# IMX7S_CPU_INTERFACES_1.net
KiCad netlist of a schematic drawn in Altium Designer
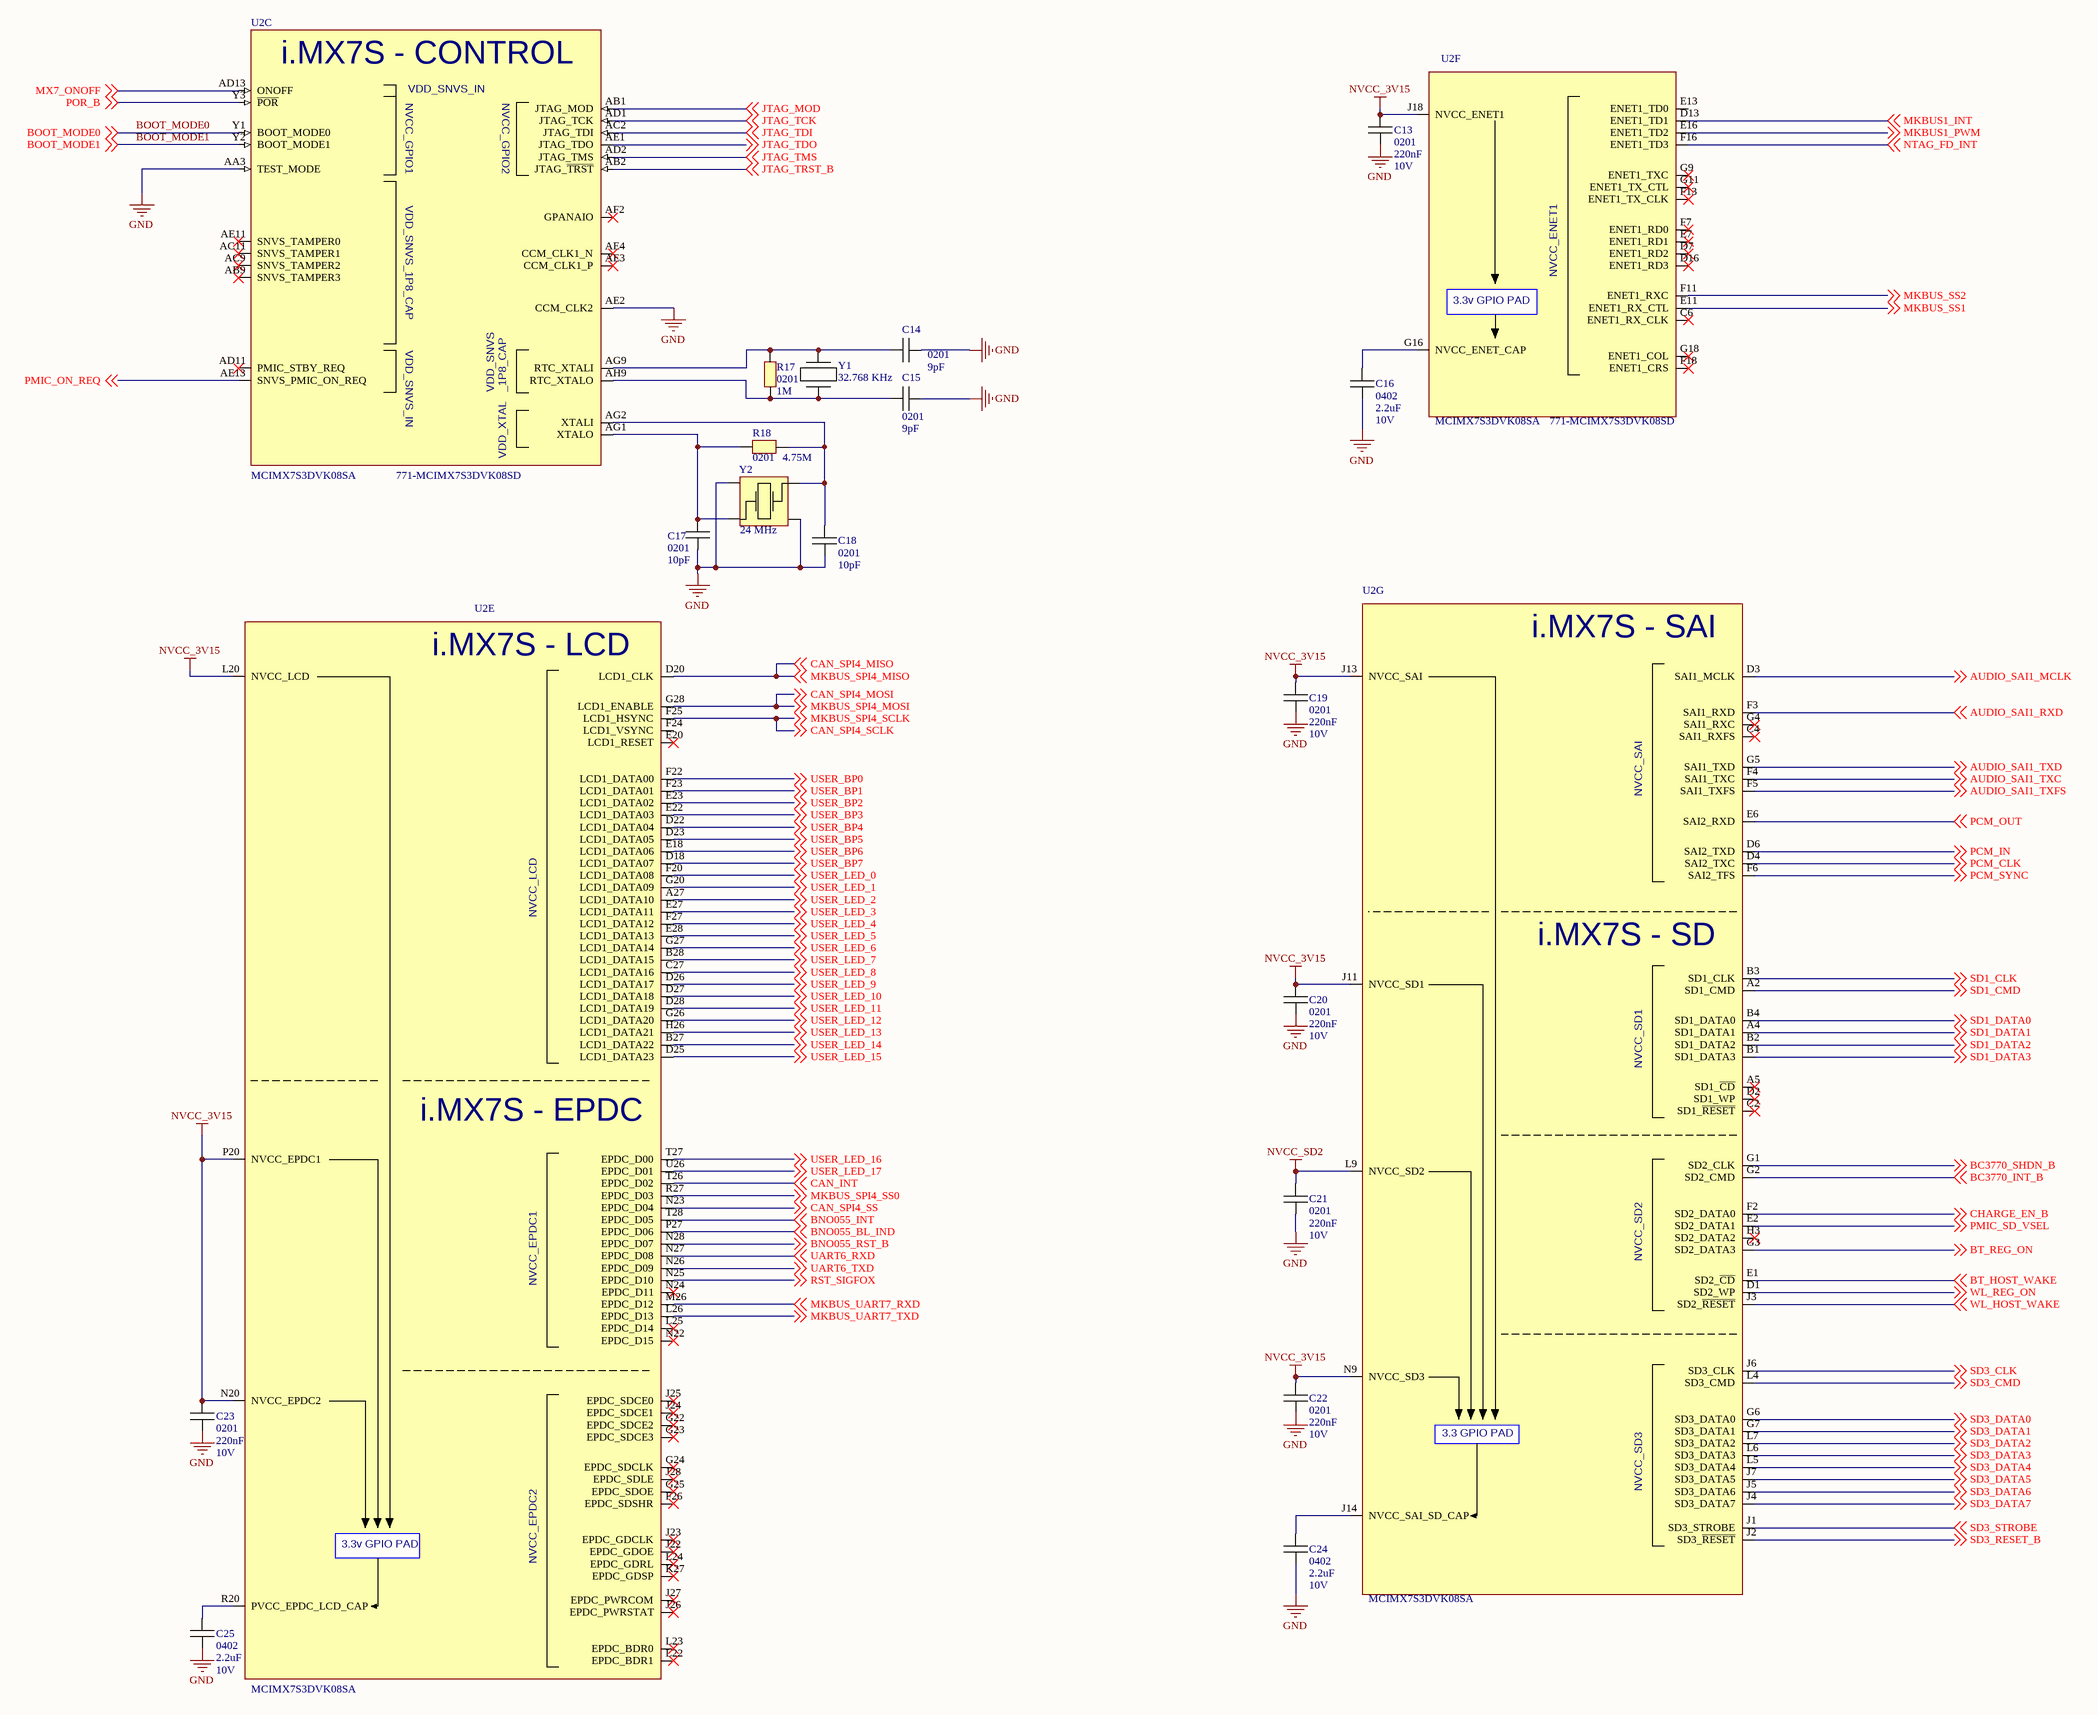
[diagram p0: IMX7S_CPU_INTERFACES_1.SchDoc]

(export (version "E")
  (design (tool "Eeschema 10.0.6"))
  (components
    (comp (ref "C13")
      (value "220nF")
      (footprint "C0201")
      (fields
        (field (name "PACKAGE") "0201")
        (field (name "VOLTAGE") "10V")
        (field (name "TOLERANCE") "10%")
        (field (name "Comment") "C0201")
      )
      (libsource (lib "Schlib_IMX7") (part "C0201"))
    )
    (comp (ref "C14")
      (value "9pF")
      (footprint "C0201")
      (description "CAP CER 9PF 25V C0G 0201")
      (fields (field (name "PACKAGE") "0201") (field (name "VOLTAGE") "0V") (field (name "Comment") "C0201"))
      (libsource (lib "Schlib_IMX7") (part "C0201"))
    )
    (comp (ref "C15")
      (value "9pF")
      (footprint "C0201")
      (description "CAP CER 9PF 25V C0G 0201")
      (fields (field (name "PACKAGE") "0201") (field (name "VOLTAGE") "0V") (field (name "Comment") "C0201"))
      (libsource (lib "Schlib_IMX7") (part "C0201"))
    )
    (comp (ref "C16")
      (value "2.2uF")
      (footprint "C0402")
      (fields
        (field (name "PACKAGE") "0402")
        (field (name "VOLTAGE") "10V")
        (field (name "TOLERANCE") "20%")
        (field (name "Comment") "C0402")
      )
      (libsource (lib "Schlib_IMX7") (part "C0402"))
    )
    (comp (ref "C17")
      (value "10pF")
      (footprint "C0201")
      (description "0201 18 pF 50 V ±2% Tolerance C0G/NP0 Multilayer Ceramic Capacitor")
      (fields (field (name "PACKAGE") "0201") (field (name "VOLTAGE") "0V") (field (name "TOLERANCE") "2%"))
      (libsource (lib "Schlib_IMX7") (part "C0201"))
    )
    (comp (ref "C18")
      (value "10pF")
      (footprint "C0201")
      (description "0201 18 pF 50 V ±2% Tolerance C0G/NP0 Multilayer Ceramic Capacitor")
      (fields (field (name "PACKAGE") "0201") (field (name "VOLTAGE") "0V") (field (name "TOLERANCE") "2%"))
      (libsource (lib "Schlib_IMX7") (part "C0201"))
    )
    (comp (ref "C19")
      (value "220nF")
      (footprint "C0201")
      (fields
        (field (name "PACKAGE") "0201")
        (field (name "VOLTAGE") "10V")
        (field (name "TOLERANCE") "10%")
        (field (name "Comment") "C0201")
      )
      (libsource (lib "Schlib_IMX7") (part "C0201"))
    )
    (comp (ref "C20")
      (value "220nF")
      (footprint "C0201")
      (fields
        (field (name "PACKAGE") "0201")
        (field (name "VOLTAGE") "10V")
        (field (name "TOLERANCE") "10%")
        (field (name "Comment") "C0201")
      )
      (libsource (lib "Schlib_IMX7") (part "C0201"))
    )
    (comp (ref "C21")
      (value "220nF")
      (footprint "C0201")
      (fields
        (field (name "PACKAGE") "0201")
        (field (name "VOLTAGE") "10V")
        (field (name "TOLERANCE") "10%")
        (field (name "Comment") "C0201")
      )
      (libsource (lib "Schlib_IMX7") (part "C0201"))
    )
    (comp (ref "C22")
      (value "220nF")
      (footprint "C0201")
      (fields
        (field (name "PACKAGE") "0201")
        (field (name "VOLTAGE") "10V")
        (field (name "TOLERANCE") "10%")
        (field (name "Comment") "C0201")
      )
      (libsource (lib "Schlib_IMX7") (part "C0201"))
    )
    (comp (ref "C23")
      (value "220nF")
      (footprint "C0201")
      (fields
        (field (name "PACKAGE") "0201")
        (field (name "VOLTAGE") "10V")
        (field (name "TOLERANCE") "10%")
        (field (name "Comment") "C0201")
      )
      (libsource (lib "Schlib_IMX7") (part "C0201"))
    )
    (comp (ref "C24")
      (value "2.2uF")
      (footprint "C0402")
      (fields
        (field (name "PACKAGE") "0402")
        (field (name "VOLTAGE") "10V")
        (field (name "TOLERANCE") "20%")
        (field (name "Comment") "C0402")
      )
      (libsource (lib "Schlib_IMX7") (part "C0402"))
    )
    (comp (ref "C25")
      (value "2.2uF")
      (footprint "C0402")
      (fields
        (field (name "PACKAGE") "0402")
        (field (name "VOLTAGE") "10V")
        (field (name "TOLERANCE") "20%")
        (field (name "Comment") "C0402")
      )
      (libsource (lib "Schlib_IMX7") (part "C0402"))
    )
    (comp (ref "R17")
      (value "1M")
      (footprint "R0201")
      (fields
        (field (name "PACKAGE") "0201")
        (field (name "VOLTAGE") "0V")
        (field (name "TOLERANCE") "1%")
        (field (name "Comment") "R0201")
      )
      (libsource (lib "Schlib_IMX7") (part "R0201"))
    )
    (comp (ref "R18")
      (value "4.75M")
      (footprint "R0201")
      (description "MULTICOMP - MC0201L6J4704SE - RES, 4M7, 5%, 0.05W, 0201, THICK FILM")
      (fields (field (name "PACKAGE") "0201") (field (name "VOLTAGE") "0V") (field (name "TOLERANCE") "5%"))
      (libsource (lib "") (part "R0201_1"))
    )
    (comp (ref "U2")
      (value "MCIMX7S3DVK08SA")
      (footprint "BGA 488 PIN")
      (fields (field (name "SUPPLIER PART NUMBER 1") "771-MCIMX7S3DVK08SD"))
      (libsource (lib "Schlib_IMX7") (part "MCIMX7S3DVK08SD"))
    )
    (comp (ref "Y1")
      (value "32.768 KHz")
      (footprint "ABS07")
      (libsource (lib "Schlib_IMX7") (part "Quartz 32.768"))
    )
    (comp (ref "Y2")
      (value "24 MHz")
      (footprint "3225 Crystal")
      (libsource (lib "Schlib_IMX7") (part "Quartz 24M"))
    )
  )
  (nets
    (net (code "1") (name "AUDIO_SAI1_MCLK") (class "Default")
      (node (ref "U2") (pin "D3") (pinfunction "SAI1_MCLK_D3") (pintype "passive"))
    )
    (net (code "2") (name "AUDIO_SAI1_RXD") (class "Default")
      (node (ref "U2") (pin "F3") (pinfunction "SAI1_RXD_F3") (pintype "passive"))
    )
    (net (code "3") (name "AUDIO_SAI1_TXC") (class "Default")
      (node (ref "U2") (pin "F4") (pinfunction "SAI1_TXC_F4") (pintype "passive"))
    )
    (net (code "4") (name "AUDIO_SAI1_TXD") (class "Default")
      (node (ref "U2") (pin "G5") (pinfunction "SAI1_TXD_G5") (pintype "passive"))
    )
    (net (code "5") (name "AUDIO_SAI1_TXFS") (class "Default")
      (node (ref "U2") (pin "F5") (pinfunction "SAI1_TXFS_F5") (pintype "passive"))
    )
    (net (code "6") (name "BC3770_INT_B") (class "Default")
      (node (ref "U2") (pin "G2") (pinfunction "SD2_CMD_G2") (pintype "passive"))
    )
    (net (code "7") (name "BC3770_SHDN_B") (class "Default")
      (node (ref "U2") (pin "G1") (pinfunction "SD2_CLK_G1") (pintype "passive"))
    )
    (net (code "8") (name "BNO055_BL_IND") (class "Default")
      (node (ref "U2") (pin "P27") (pinfunction "EPDC_D06_P27") (pintype "passive"))
    )
    (net (code "9") (name "BNO055_INT") (class "Default")
      (node (ref "U2") (pin "T28") (pinfunction "EPDC_D05_T28") (pintype "passive"))
    )
    (net (code "10") (name "BNO055_RST_B") (class "Default")
      (node (ref "U2") (pin "N28") (pinfunction "EPDC_D07_N28") (pintype "passive"))
    )
    (net (code "11") (name "BOOT_MODE0") (class "Default")
      (node (ref "U2") (pin "Y1") (pinfunction "BOOT_MODE0_Y1") (pintype "input"))
    )
    (net (code "12") (name "BOOT_MODE1") (class "Default")
      (node (ref "U2") (pin "Y2") (pinfunction "BOOT_MODE1_Y2") (pintype "input"))
    )
    (net (code "13") (name "BT_HOST_WAKE") (class "Default")
      (node (ref "U2") (pin "E1") (pinfunction "SD2_~{CD}_E1") (pintype "passive"))
    )
    (net (code "14") (name "BT_REG_ON") (class "Default")
      (node (ref "U2") (pin "G3") (pinfunction "SD2_DATA3_G3") (pintype "passive"))
    )
    (net (code "15") (name "CAN_INT") (class "Default")
      (node (ref "U2") (pin "T26") (pinfunction "EPDC_D02_T26") (pintype "passive"))
    )
    (net (code "16") (name "CAN_SPI4_MISO") (class "Default")
      (node (ref "U2") (pin "D20") (pinfunction "LCD1_CLK_D20") (pintype "passive"))
    )
    (net (code "17") (name "CAN_SPI4_MOSI") (class "Default")
      (node (ref "U2") (pin "G28") (pinfunction "LCD1_ENABLE_G28") (pintype "passive"))
    )
    (net (code "18") (name "CAN_SPI4_SCLK") (class "Default")
      (node (ref "U2") (pin "F25") (pinfunction "LCD1_HSYNC_F25") (pintype "passive"))
    )
    (net (code "19") (name "CAN_SPI4_SS") (class "Default")
      (node (ref "U2") (pin "N23") (pinfunction "EPDC_D04_N23") (pintype "passive"))
    )
    (net (code "20") (name "CHARGE_EN_B") (class "Default")
      (node (ref "U2") (pin "F2") (pinfunction "SD2_DATA0_F2") (pintype "passive"))
    )
    (net (code "21") (name "GND") (class "Default")
      (node (ref "C13") (pin "1") (pinfunction "1_1") (pintype "passive"))
      (node (ref "C14") (pin "1") (pinfunction "1_1") (pintype "passive"))
      (node (ref "C15") (pin "1") (pinfunction "1_1") (pintype "passive"))
      (node (ref "C16") (pin "1") (pinfunction "1_1") (pintype "passive"))
      (node (ref "C17") (pin "1") (pinfunction "1_1") (pintype "passive"))
      (node (ref "C18") (pin "1") (pinfunction "1_1") (pintype "passive"))
      (node (ref "C19") (pin "1") (pinfunction "1_1") (pintype "passive"))
      (node (ref "C20") (pin "1") (pinfunction "1_1") (pintype "passive"))
      (node (ref "C21") (pin "1") (pinfunction "1_1") (pintype "passive"))
      (node (ref "C22") (pin "1") (pinfunction "1_1") (pintype "passive"))
      (node (ref "C23") (pin "1") (pinfunction "1_1") (pintype "passive"))
      (node (ref "C24") (pin "1") (pinfunction "1_1") (pintype "passive"))
      (node (ref "C25") (pin "1") (pinfunction "1_1") (pintype "passive"))
      (node (ref "U2") (pin "AA3") (pinfunction "TEST_MODE_AA3") (pintype "input"))
      (node (ref "U2") (pin "AE2") (pinfunction "CCM_CLK2_AE2") (pintype "passive"))
      (node (ref "Y2") (pin "1") (pintype "passive"))
      (node (ref "Y2") (pin "3") (pintype "passive"))
    )
    (net (code "22") (name "JTAG_MOD") (class "Default")
      (node (ref "U2") (pin "AB1") (pinfunction "JTAG_MOD_AB1") (pintype "input"))
    )
    (net (code "23") (name "JTAG_TCK") (class "Default")
      (node (ref "U2") (pin "AD1") (pinfunction "JTAG_TCK_AD1") (pintype "input"))
    )
    (net (code "24") (name "JTAG_TDI") (class "Default")
      (node (ref "U2") (pin "AC2") (pinfunction "JTAG_TDI_AC2") (pintype "input"))
    )
    (net (code "25") (name "JTAG_TDO") (class "Default")
      (node (ref "U2") (pin "AE1") (pinfunction "JTAG_TDO_AE1") (pintype "passive"))
    )
    (net (code "26") (name "JTAG_TMS") (class "Default")
      (node (ref "U2") (pin "AD2") (pinfunction "JTAG_TMS_AD2") (pintype "input"))
    )
    (net (code "27") (name "JTAG_TRST_B") (class "Default")
      (node (ref "U2") (pin "AB2") (pinfunction "JTAG_~{TRST}_AB2") (pintype "input"))
    )
    (net (code "28") (name "MKBUS1_INT") (class "Default")
      (node (ref "U2") (pin "D13") (pinfunction "ENET1_TD1_D13") (pintype "passive"))
    )
    (net (code "29") (name "MKBUS1_PWM") (class "Default")
      (node (ref "U2") (pin "E16") (pinfunction "ENET1_TD2_E16") (pintype "passive"))
    )
    (net (code "30") (name "MKBUS_SPI4_SS0") (class "Default")
      (node (ref "U2") (pin "R27") (pinfunction "EPDC_D03_R27") (pintype "passive"))
    )
    (net (code "31") (name "MKBUS_SS1") (class "Default")
      (node (ref "U2") (pin "E11") (pinfunction "ENET1_RX_CTL_E11") (pintype "passive"))
    )
    (net (code "32") (name "MKBUS_SS2") (class "Default")
      (node (ref "U2") (pin "F11") (pinfunction "ENET1_RXC_F11") (pintype "passive"))
    )
    (net (code "33") (name "MKBUS_UART7_RXD") (class "Default")
      (node (ref "U2") (pin "M26") (pinfunction "EPDC_D12_M26") (pintype "passive"))
    )
    (net (code "34") (name "MKBUS_UART7_TXD") (class "Default")
      (node (ref "U2") (pin "L26") (pinfunction "EPDC_D13_L26") (pintype "passive"))
    )
    (net (code "35") (name "MX7_ONOFF") (class "Default")
      (node (ref "U2") (pin "AD13") (pinfunction "ONOFF_AD13") (pintype "input"))
    )
    (net (code "36") (name "NTAG_FD_INT") (class "Default")
      (node (ref "U2") (pin "F16") (pinfunction "ENET1_TD3_F16") (pintype "passive"))
    )
    (net (code "37") (name "NVCC_3V15") (class "Default")
      (node (ref "C13") (pin "2") (pinfunction "2_2") (pintype "passive"))
      (node (ref "C19") (pin "2") (pinfunction "2_2") (pintype "passive"))
      (node (ref "C20") (pin "2") (pinfunction "2_2") (pintype "passive"))
      (node (ref "C22") (pin "2") (pinfunction "2_2") (pintype "passive"))
      (node (ref "C23") (pin "2") (pinfunction "2_2") (pintype "passive"))
      (node (ref "U2") (pin "J11") (pinfunction "NVCC_SD1_J11") (pintype "passive"))
      (node (ref "U2") (pin "J13") (pinfunction "NVCC_SAI_J13") (pintype "passive"))
      (node (ref "U2") (pin "J18") (pinfunction "NVCC_ENET1_J18") (pintype "passive"))
      (node (ref "U2") (pin "L20") (pinfunction "NVCC_LCD_L20") (pintype "passive"))
      (node (ref "U2") (pin "N20") (pinfunction "NVCC_EPDC2_N20") (pintype "passive"))
      (node (ref "U2") (pin "N9") (pinfunction "NVCC_SD3_N9") (pintype "passive"))
      (node (ref "U2") (pin "P20") (pinfunction "NVCC_EPDC1_P20") (pintype "passive"))
    )
    (net (code "38") (name "NVCC_SD2") (class "Default")
      (node (ref "C21") (pin "2") (pinfunction "2_2") (pintype "passive"))
      (node (ref "U2") (pin "L9") (pinfunction "NVCC_SD2_L9") (pintype "passive"))
    )
    (net (code "39") (name "Net-(U2C-RTC_XTALI)") (class "Default")
      (node (ref "C14") (pin "2") (pinfunction "2_2") (pintype "passive"))
      (node (ref "R17") (pin "2") (pinfunction "2_2") (pintype "passive"))
      (node (ref "U2") (pin "AG9") (pinfunction "RTC_XTALI_AG9") (pintype "passive"))
      (node (ref "Y1") (pin "2") (pintype "passive"))
    )
    (net (code "40") (name "Net-(U2C-RTC_XTALO)") (class "Default")
      (node (ref "C15") (pin "2") (pinfunction "2_2") (pintype "passive"))
      (node (ref "R17") (pin "1") (pinfunction "1_1") (pintype "passive"))
      (node (ref "U2") (pin "AH9") (pinfunction "RTC_XTALO_AH9") (pintype "passive"))
      (node (ref "Y1") (pin "1") (pintype "passive"))
    )
    (net (code "41") (name "Net-(U2C-XTALI)") (class "Default")
      (node (ref "C18") (pin "2") (pinfunction "2_2") (pintype "passive"))
      (node (ref "R18") (pin "1") (pinfunction "1_1") (pintype "passive"))
      (node (ref "U2") (pin "AG2") (pinfunction "XTALI_AG2") (pintype "passive"))
      (node (ref "Y2") (pin "4") (pintype "passive"))
    )
    (net (code "42") (name "Net-(U2C-XTALO)") (class "Default")
      (node (ref "C17") (pin "2") (pinfunction "2_2") (pintype "passive"))
      (node (ref "R18") (pin "2") (pinfunction "2_2") (pintype "passive"))
      (node (ref "U2") (pin "AG1") (pinfunction "XTALO_AG1") (pintype "passive"))
      (node (ref "Y2") (pin "2") (pintype "passive"))
    )
    (net (code "43") (name "Net-(U2E-PVCC_EPDC_LCD_CAP)") (class "Default")
      (node (ref "C25") (pin "2") (pinfunction "2_2") (pintype "passive"))
      (node (ref "U2") (pin "R20") (pinfunction "PVCC_EPDC_LCD_CAP_R20") (pintype "passive"))
    )
    (net (code "44") (name "Net-(U2F-NVCC_ENET_CAP)") (class "Default")
      (node (ref "C16") (pin "2") (pinfunction "2_2") (pintype "passive"))
      (node (ref "U2") (pin "G16") (pinfunction "NVCC_ENET_CAP_G16") (pintype "passive"))
    )
    (net (code "45") (name "Net-(U2G-NVCC_SAI_SD_CAP)") (class "Default")
      (node (ref "C24") (pin "2") (pinfunction "2_2") (pintype "passive"))
      (node (ref "U2") (pin "J14") (pinfunction "NVCC_SAI_SD_CAP_J14") (pintype "passive"))
    )
    (net (code "46") (name "PCM_CLK") (class "Default")
      (node (ref "U2") (pin "D4") (pinfunction "SAI2_TXC_D4") (pintype "passive"))
    )
    (net (code "47") (name "PCM_IN") (class "Default")
      (node (ref "U2") (pin "D6") (pinfunction "SAI2_TXD_D6") (pintype "passive"))
    )
    (net (code "48") (name "PCM_OUT") (class "Default")
      (node (ref "U2") (pin "E6") (pinfunction "SAI2_RXD_E6") (pintype "passive"))
    )
    (net (code "49") (name "PCM_SYNC") (class "Default")
      (node (ref "U2") (pin "F6") (pinfunction "SAI2_TFS_F6") (pintype "passive"))
    )
    (net (code "50") (name "PMIC_ON_REQ") (class "Default")
      (node (ref "U2") (pin "AE13") (pinfunction "SNVS_PMIC_ON_REQ_AE13") (pintype "passive"))
    )
    (net (code "51") (name "PMIC_SD_VSEL") (class "Default")
      (node (ref "U2") (pin "E2") (pinfunction "SD2_DATA1_E2") (pintype "passive"))
    )
    (net (code "52") (name "POR_B") (class "Default")
      (node (ref "U2") (pin "Y3") (pinfunction "~{POR}_Y3") (pintype "input"))
    )
    (net (code "53") (name "RST_SIGFOX") (class "Default")
      (node (ref "U2") (pin "N25") (pinfunction "EPDC_D10_N25") (pintype "passive"))
    )
    (net (code "54") (name "SD1_CLK") (class "Default")
      (node (ref "U2") (pin "B3") (pinfunction "SD1_CLK_B3") (pintype "passive"))
    )
    (net (code "55") (name "SD1_CMD") (class "Default")
      (node (ref "U2") (pin "A2") (pinfunction "SD1_CMD_A2") (pintype "passive"))
    )
    (net (code "56") (name "SD1_DATA0") (class "Default")
      (node (ref "U2") (pin "B4") (pinfunction "SD1_DATA0_B4") (pintype "passive"))
    )
    (net (code "57") (name "SD1_DATA1") (class "Default")
      (node (ref "U2") (pin "A4") (pinfunction "SD1_DATA1_A4") (pintype "passive"))
    )
    (net (code "58") (name "SD1_DATA2") (class "Default")
      (node (ref "U2") (pin "B2") (pinfunction "SD1_DATA2_B2") (pintype "passive"))
    )
    (net (code "59") (name "SD1_DATA3") (class "Default")
      (node (ref "U2") (pin "B1") (pinfunction "SD1_DATA3_B1") (pintype "passive"))
    )
    (net (code "60") (name "SD3_CLK") (class "Default")
      (node (ref "U2") (pin "J6") (pinfunction "SD3_CLK_J6") (pintype "passive"))
    )
    (net (code "61") (name "SD3_CMD") (class "Default")
      (node (ref "U2") (pin "L4") (pinfunction "SD3_CMD_L4") (pintype "passive"))
    )
    (net (code "62") (name "SD3_DATA0") (class "Default")
      (node (ref "U2") (pin "G6") (pinfunction "SD3_DATA0_G6") (pintype "passive"))
    )
    (net (code "63") (name "SD3_DATA1") (class "Default")
      (node (ref "U2") (pin "G7") (pinfunction "SD3_DATA1_G7") (pintype "passive"))
    )
    (net (code "64") (name "SD3_DATA2") (class "Default")
      (node (ref "U2") (pin "L7") (pinfunction "SD3_DATA2_L7") (pintype "passive"))
    )
    (net (code "65") (name "SD3_DATA3") (class "Default")
      (node (ref "U2") (pin "L6") (pinfunction "SD3_DATA3_L6") (pintype "passive"))
    )
    (net (code "66") (name "SD3_DATA4") (class "Default")
      (node (ref "U2") (pin "L5") (pinfunction "SD3_DATA4_L5") (pintype "passive"))
    )
    (net (code "67") (name "SD3_DATA5") (class "Default")
      (node (ref "U2") (pin "J7") (pinfunction "SD3_DATA5_J7") (pintype "passive"))
    )
    (net (code "68") (name "SD3_DATA6") (class "Default")
      (node (ref "U2") (pin "J5") (pinfunction "SD3_DATA6_J5") (pintype "passive"))
    )
    (net (code "69") (name "SD3_DATA7") (class "Default")
      (node (ref "U2") (pin "J4") (pinfunction "SD3_DATA7_J4") (pintype "passive"))
    )
    (net (code "70") (name "SD3_RESET_B") (class "Default")
      (node (ref "U2") (pin "J2") (pinfunction "SD3_~{RESET}_J2") (pintype "passive"))
    )
    (net (code "71") (name "SD3_STROBE") (class "Default")
      (node (ref "U2") (pin "J1") (pinfunction "SD3_STROBE_J1") (pintype "passive"))
    )
    (net (code "72") (name "UART6_RXD") (class "Default")
      (node (ref "U2") (pin "N27") (pinfunction "EPDC_D08_N27") (pintype "passive"))
    )
    (net (code "73") (name "UART6_TXD") (class "Default")
      (node (ref "U2") (pin "N26") (pinfunction "EPDC_D09_N26") (pintype "passive"))
    )
    (net (code "74") (name "USER_BP0") (class "Default")
      (node (ref "U2") (pin "F22") (pinfunction "LCD1_DATA00_F22") (pintype "passive"))
    )
    (net (code "75") (name "USER_BP1") (class "Default")
      (node (ref "U2") (pin "F23") (pinfunction "LCD1_DATA01_F23") (pintype "passive"))
    )
    (net (code "76") (name "USER_BP2") (class "Default")
      (node (ref "U2") (pin "E23") (pinfunction "LCD1_DATA02_E23") (pintype "passive"))
    )
    (net (code "77") (name "USER_BP3") (class "Default")
      (node (ref "U2") (pin "E22") (pinfunction "LCD1_DATA03_E22") (pintype "passive"))
    )
    (net (code "78") (name "USER_BP4") (class "Default")
      (node (ref "U2") (pin "D22") (pinfunction "LCD1_DATA04_D22") (pintype "passive"))
    )
    (net (code "79") (name "USER_BP5") (class "Default")
      (node (ref "U2") (pin "D23") (pinfunction "LCD1_DATA05_D23") (pintype "passive"))
    )
    (net (code "80") (name "USER_BP6") (class "Default")
      (node (ref "U2") (pin "E18") (pinfunction "LCD1_DATA06_E18") (pintype "passive"))
    )
    (net (code "81") (name "USER_BP7") (class "Default")
      (node (ref "U2") (pin "D18") (pinfunction "LCD1_DATA07_D18") (pintype "passive"))
    )
    (net (code "82") (name "USER_LED_0") (class "Default")
      (node (ref "U2") (pin "F20") (pinfunction "LCD1_DATA08_F20") (pintype "passive"))
    )
    (net (code "83") (name "USER_LED_1") (class "Default")
      (node (ref "U2") (pin "G20") (pinfunction "LCD1_DATA09_G20") (pintype "passive"))
    )
    (net (code "84") (name "USER_LED_2") (class "Default")
      (node (ref "U2") (pin "A27") (pinfunction "LCD1_DATA10_A27") (pintype "passive"))
    )
    (net (code "85") (name "USER_LED_3") (class "Default")
      (node (ref "U2") (pin "E27") (pinfunction "LCD1_DATA11_E27") (pintype "passive"))
    )
    (net (code "86") (name "USER_LED_4") (class "Default")
      (node (ref "U2") (pin "F27") (pinfunction "LCD1_DATA12_F27") (pintype "passive"))
    )
    (net (code "87") (name "USER_LED_5") (class "Default")
      (node (ref "U2") (pin "E28") (pinfunction "LCD1_DATA13_E28") (pintype "passive"))
    )
    (net (code "88") (name "USER_LED_6") (class "Default")
      (node (ref "U2") (pin "G27") (pinfunction "LCD1_DATA14_G27") (pintype "passive"))
    )
    (net (code "89") (name "USER_LED_7") (class "Default")
      (node (ref "U2") (pin "B28") (pinfunction "LCD1_DATA15_B28") (pintype "passive"))
    )
    (net (code "90") (name "USER_LED_8") (class "Default")
      (node (ref "U2") (pin "C27") (pinfunction "LCD1_DATA16_C27") (pintype "passive"))
    )
    (net (code "91") (name "USER_LED_9") (class "Default")
      (node (ref "U2") (pin "D26") (pinfunction "LCD1_DATA17_D26") (pintype "passive"))
    )
    (net (code "92") (name "USER_LED_10") (class "Default")
      (node (ref "U2") (pin "D27") (pinfunction "LCD1_DATA18_D27") (pintype "passive"))
    )
    (net (code "93") (name "USER_LED_11") (class "Default")
      (node (ref "U2") (pin "D28") (pinfunction "LCD1_DATA19_D28") (pintype "passive"))
    )
    (net (code "94") (name "USER_LED_12") (class "Default")
      (node (ref "U2") (pin "G26") (pinfunction "LCD1_DATA20_G26") (pintype "passive"))
    )
    (net (code "95") (name "USER_LED_13") (class "Default")
      (node (ref "U2") (pin "H26") (pinfunction "LCD1_DATA21_H26") (pintype "passive"))
    )
    (net (code "96") (name "USER_LED_14") (class "Default")
      (node (ref "U2") (pin "B27") (pinfunction "LCD1_DATA22_B27") (pintype "passive"))
    )
    (net (code "97") (name "USER_LED_15") (class "Default")
      (node (ref "U2") (pin "D25") (pinfunction "LCD1_DATA23_D25") (pintype "passive"))
    )
    (net (code "98") (name "USER_LED_16") (class "Default")
      (node (ref "U2") (pin "T27") (pinfunction "EPDC_D00_T27") (pintype "passive"))
    )
    (net (code "99") (name "USER_LED_17") (class "Default")
      (node (ref "U2") (pin "U26") (pinfunction "EPDC_D01_U26") (pintype "passive"))
    )
    (net (code "100") (name "WL_HOST_WAKE") (class "Default")
      (node (ref "U2") (pin "J3") (pinfunction "SD2_~{RESET}_J3") (pintype "passive"))
    )
    (net (code "101") (name "WL_REG_ON") (class "Default")
      (node (ref "U2") (pin "D1") (pinfunction "SD2_WP_D1") (pintype "passive"))
    )
    (net (code "102") (name "unconnected-(U2C-CCM_CLK1_N-PadAE4)") (class "Default")
      (node (ref "U2") (pin "AE4") (pinfunction "CCM_CLK1_N_AE4") (pintype "passive+no_connect"))
    )
    (net (code "103") (name "unconnected-(U2C-CCM_CLK1_P-PadAE3)") (class "Default")
      (node (ref "U2") (pin "AE3") (pinfunction "CCM_CLK1_P_AE3") (pintype "passive+no_connect"))
    )
    (net (code "104") (name "unconnected-(U2C-GPANAIO-PadAF2)") (class "Default")
      (node (ref "U2") (pin "AF2") (pinfunction "GPANAIO_AF2") (pintype "passive+no_connect"))
    )
    (net (code "105") (name "unconnected-(U2C-PMIC_STBY_REQ-PadAD11)") (class "Default")
      (node (ref "U2") (pin "AD11") (pinfunction "PMIC_STBY_REQ_AD11") (pintype "passive+no_connect"))
    )
    (net (code "106") (name "unconnected-(U2C-SNVS_TAMPER0-PadAE11)") (class "Default")
      (node (ref "U2") (pin "AE11") (pinfunction "SNVS_TAMPER0_AE11") (pintype "passive+no_connect"))
    )
    (net (code "107") (name "unconnected-(U2C-SNVS_TAMPER1-PadAC11)") (class "Default")
      (node (ref "U2") (pin "AC11") (pinfunction "SNVS_TAMPER1_AC11") (pintype "passive+no_connect"))
    )
    (net (code "108") (name "unconnected-(U2C-SNVS_TAMPER2-PadAC9)") (class "Default")
      (node (ref "U2") (pin "AC9") (pinfunction "SNVS_TAMPER2_AC9") (pintype "passive+no_connect"))
    )
    (net (code "109") (name "unconnected-(U2C-SNVS_TAMPER3-PadAB9)") (class "Default")
      (node (ref "U2") (pin "AB9") (pinfunction "SNVS_TAMPER3_AB9") (pintype "passive+no_connect"))
    )
    (net (code "110") (name "unconnected-(U2E-EPDC_BDR0-PadL23)") (class "Default")
      (node (ref "U2") (pin "L23") (pinfunction "EPDC_BDR0_L23") (pintype "passive+no_connect"))
    )
    (net (code "111") (name "unconnected-(U2E-EPDC_BDR1-PadL22)") (class "Default")
      (node (ref "U2") (pin "L22") (pinfunction "EPDC_BDR1_L22") (pintype "passive+no_connect"))
    )
    (net (code "112") (name "unconnected-(U2E-EPDC_D11-PadN24)") (class "Default")
      (node (ref "U2") (pin "N24") (pinfunction "EPDC_D11_N24") (pintype "passive+no_connect"))
    )
    (net (code "113") (name "unconnected-(U2E-EPDC_D14-PadL25)") (class "Default")
      (node (ref "U2") (pin "L25") (pinfunction "EPDC_D14_L25") (pintype "passive+no_connect"))
    )
    (net (code "114") (name "unconnected-(U2E-EPDC_D15-PadN22)") (class "Default")
      (node (ref "U2") (pin "N22") (pinfunction "EPDC_D15_N22") (pintype "passive+no_connect"))
    )
    (net (code "115") (name "unconnected-(U2E-EPDC_GDCLK-PadJ23)") (class "Default")
      (node (ref "U2") (pin "J23") (pinfunction "EPDC_GDCLK_J23") (pintype "passive+no_connect"))
    )
    (net (code "116") (name "unconnected-(U2E-EPDC_GDOE-PadJ22)") (class "Default")
      (node (ref "U2") (pin "J22") (pinfunction "EPDC_GDOE_J22") (pintype "passive+no_connect"))
    )
    (net (code "117") (name "unconnected-(U2E-EPDC_GDRL-PadL24)") (class "Default")
      (node (ref "U2") (pin "L24") (pinfunction "EPDC_GDRL_L24") (pintype "passive+no_connect"))
    )
    (net (code "118") (name "unconnected-(U2E-EPDC_GDSP-PadK27)") (class "Default")
      (node (ref "U2") (pin "K27") (pinfunction "EPDC_GDSP_K27") (pintype "passive+no_connect"))
    )
    (net (code "119") (name "unconnected-(U2E-EPDC_PWRCOM-PadJ27)") (class "Default")
      (node (ref "U2") (pin "J27") (pinfunction "EPDC_PWRCOM_J27") (pintype "passive+no_connect"))
    )
    (net (code "120") (name "unconnected-(U2E-EPDC_PWRSTAT-PadJ26)") (class "Default")
      (node (ref "U2") (pin "J26") (pinfunction "EPDC_PWRSTAT_J26") (pintype "passive+no_connect"))
    )
    (net (code "121") (name "unconnected-(U2E-EPDC_SDCE0-PadJ25)") (class "Default")
      (node (ref "U2") (pin "J25") (pinfunction "EPDC_SDCE0_J25") (pintype "passive+no_connect"))
    )
    (net (code "122") (name "unconnected-(U2E-EPDC_SDCE1-PadJ24)") (class "Default")
      (node (ref "U2") (pin "J24") (pinfunction "EPDC_SDCE1_J24") (pintype "passive+no_connect"))
    )
    (net (code "123") (name "unconnected-(U2E-EPDC_SDCE2-PadG22)") (class "Default")
      (node (ref "U2") (pin "G22") (pinfunction "EPDC_SDCE2_G22") (pintype "passive+no_connect"))
    )
    (net (code "124") (name "unconnected-(U2E-EPDC_SDCE3-PadG23)") (class "Default")
      (node (ref "U2") (pin "G23") (pinfunction "EPDC_SDCE3_G23") (pintype "passive+no_connect"))
    )
    (net (code "125") (name "unconnected-(U2E-EPDC_SDCLK-PadG24)") (class "Default")
      (node (ref "U2") (pin "G24") (pinfunction "EPDC_SDCLK_G24") (pintype "passive+no_connect"))
    )
    (net (code "126") (name "unconnected-(U2E-EPDC_SDLE-PadJ28)") (class "Default")
      (node (ref "U2") (pin "J28") (pinfunction "EPDC_SDLE_J28") (pintype "passive+no_connect"))
    )
    (net (code "127") (name "unconnected-(U2E-EPDC_SDOE-PadG25)") (class "Default")
      (node (ref "U2") (pin "G25") (pinfunction "EPDC_SDOE_G25") (pintype "passive+no_connect"))
    )
    (net (code "128") (name "unconnected-(U2E-EPDC_SDSHR-PadF26)") (class "Default")
      (node (ref "U2") (pin "F26") (pinfunction "EPDC_SDSHR_F26") (pintype "passive+no_connect"))
    )
    (net (code "129") (name "unconnected-(U2E-LCD1_RESET-PadE20)") (class "Default")
      (node (ref "U2") (pin "E20") (pinfunction "LCD1_RESET_E20") (pintype "passive+no_connect"))
    )
    (net (code "130") (name "unconnected-(U2E-LCD1_VSYNC-PadF24)") (class "Default")
      (node (ref "U2") (pin "F24") (pinfunction "LCD1_VSYNC_F24") (pintype "passive"))
    )
    (net (code "131") (name "unconnected-(U2F-ENET1_COL-PadG18)") (class "Default")
      (node (ref "U2") (pin "G18") (pinfunction "ENET1_COL_G18") (pintype "passive+no_connect"))
    )
    (net (code "132") (name "unconnected-(U2F-ENET1_CRS-PadF18)") (class "Default")
      (node (ref "U2") (pin "F18") (pinfunction "ENET1_CRS_F18") (pintype "passive+no_connect"))
    )
    (net (code "133") (name "unconnected-(U2F-ENET1_RD0-PadF7)") (class "Default")
      (node (ref "U2") (pin "F7") (pinfunction "ENET1_RD0_F7") (pintype "passive+no_connect"))
    )
    (net (code "134") (name "unconnected-(U2F-ENET1_RD1-PadE7)") (class "Default")
      (node (ref "U2") (pin "E7") (pinfunction "ENET1_RD1_E7") (pintype "passive+no_connect"))
    )
    (net (code "135") (name "unconnected-(U2F-ENET1_RD2-PadD7)") (class "Default")
      (node (ref "U2") (pin "D7") (pinfunction "ENET1_RD2_D7") (pintype "passive+no_connect"))
    )
    (net (code "136") (name "unconnected-(U2F-ENET1_RD3-PadD16)") (class "Default")
      (node (ref "U2") (pin "D16") (pinfunction "ENET1_RD3_D16") (pintype "passive+no_connect"))
    )
    (net (code "137") (name "unconnected-(U2F-ENET1_RX_CLK-PadC6)") (class "Default")
      (node (ref "U2") (pin "C6") (pinfunction "ENET1_RX_CLK_C6") (pintype "passive+no_connect"))
    )
    (net (code "138") (name "unconnected-(U2F-ENET1_TD0-PadE13)") (class "Default")
      (node (ref "U2") (pin "E13") (pinfunction "ENET1_TD0_E13") (pintype "passive"))
    )
    (net (code "139") (name "unconnected-(U2F-ENET1_TXC-PadG9)") (class "Default")
      (node (ref "U2") (pin "G9") (pinfunction "ENET1_TXC_G9") (pintype "passive+no_connect"))
    )
    (net (code "140") (name "unconnected-(U2F-ENET1_TX_CLK-PadF13)") (class "Default")
      (node (ref "U2") (pin "F13") (pinfunction "ENET1_TX_CLK_F13") (pintype "passive+no_connect"))
    )
    (net (code "141") (name "unconnected-(U2F-ENET1_TX_CTL-PadG11)") (class "Default")
      (node (ref "U2") (pin "G11") (pinfunction "ENET1_TX_CTL_G11") (pintype "passive+no_connect"))
    )
    (net (code "142") (name "unconnected-(U2G-SAI1_RXC-PadG4)") (class "Default")
      (node (ref "U2") (pin "G4") (pinfunction "SAI1_RXC_G4") (pintype "passive+no_connect"))
    )
    (net (code "143") (name "unconnected-(U2G-SAI1_RXFS-PadC4)") (class "Default")
      (node (ref "U2") (pin "C4") (pinfunction "SAI1_RXFS_C4") (pintype "passive+no_connect"))
    )
    (net (code "144") (name "unconnected-(U2G-SD1_WP-PadD2)") (class "Default")
      (node (ref "U2") (pin "D2") (pinfunction "SD1_WP_D2") (pintype "passive+no_connect"))
    )
    (net (code "145") (name "unconnected-(U2G-SD1_~{CD}-PadA5)") (class "Default")
      (node (ref "U2") (pin "A5") (pinfunction "SD1_~{CD}_A5") (pintype "passive+no_connect"))
    )
    (net (code "146") (name "unconnected-(U2G-SD1_~{RESET}-PadC2)") (class "Default")
      (node (ref "U2") (pin "C2") (pinfunction "SD1_~{RESET}_C2") (pintype "passive+no_connect"))
    )
    (net (code "147") (name "unconnected-(U2G-SD2_DATA2-PadH3)") (class "Default")
      (node (ref "U2") (pin "H3") (pinfunction "SD2_DATA2_H3") (pintype "passive+no_connect"))
    )
  )
)
